# pir_sensor.net
KiCad netlist of a schematic drawn in Altium Designer
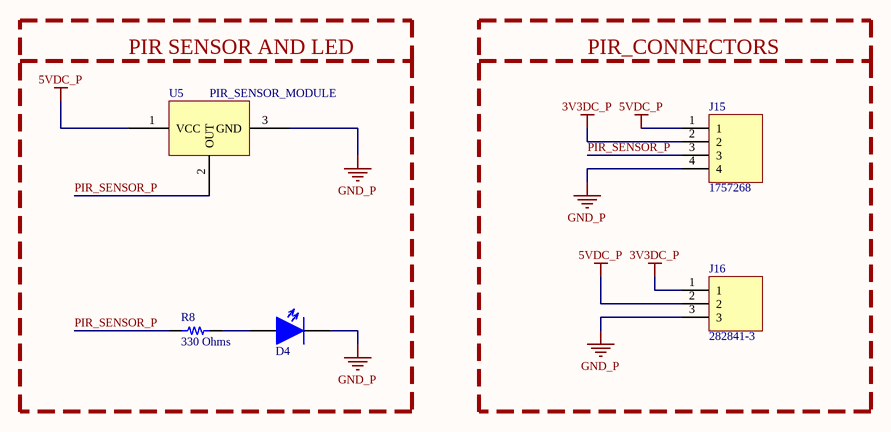
[diagram p0: pir_sensor.SchDoc]

(export (version "E")
  (design (tool "Eeschema 10.0.6"))
  (components
    (comp (ref "D4")
      (value "LTST-C171GKT")
      (footprint "LED_GREEN_0805")
      (description "Green 569nm LED Indication - Discrete 2.1V 0805 (2012 Metric)")
      (fields (field (name "MANUFACTURER") "Vishay Lite-On") (field (name "DESIGNED BY") "EMRE"))
      (libsource (lib "Udemy_library_Integrated_Library1") (part "LED GREEN 0805"))
    )
    (comp (ref "J15")
      (value "1757268")
      (footprint "CONNECTOR_4Pin")
      (description "Terminal Header; 12 A; 5.08 mm; 4; Solder Mount; 1.4 mm; 4 kV; 250 V; PBT")
      (fields (field (name "MANUFACTURER") "Phoenix Contact") (field (name "VOLTAGE") "300V"))
      (libsource (lib "Udemy_library_Integrated_Library1") (part "CONNECTOR_4Pin"))
    )
    (comp (ref "J16")
      (value "282841-3")
      (footprint "CONNECTOR_3Pin")
      (description "Conn Terminal Block 3 POS 5.08mm Solder ST Thru-Hole 17.5A/Contact")
      (fields (field (name "MANUFACTURER") "TE Connectivity") (field (name "VOLTAGE") "300V"))
      (libsource (lib "Udemy_library_Integrated_Library1") (part "CONNECTOR_3Pin"))
    )
    (comp (ref "R8")
      (value "330 Ohms")
      (footprint "RES 0805_2012")
      (description "RES SMD 330 OHM 5% 0.4W 0805")
      (fields (field (name "PART NUMBER") "ESR10EZPJ331") (field (name "MANUFACTURER") "Rohm Semiconductor"))
      (libsource (lib "Celestial Altium Library - altium_library") (part "Resistor"))
    )
    (comp (ref "U5")
      (value "PIR_SENSOR_MODULE")
      (footprint "PIR_SENSOR_MODULE")
      (libsource (lib "Udemy_library_Integrated_Library1") (part "PIR_SENSOR_MODULE"))
    )
  )
  (nets
    (net (code "1") (name "/PIR_SENSOR_P") (class "Default")
      (node (ref "J15") (pin "3") (pinfunction "3_3") (pintype "passive"))
      (node (ref "R8") (pin "1") (pinfunction "1_1") (pintype "passive"))
      (node (ref "U5") (pin "2") (pinfunction "OUT_2") (pintype "passive"))
    )
    (net (code "2") (name "3V3DC_P") (class "Default")
      (node (ref "J15") (pin "2") (pinfunction "2_2") (pintype "passive"))
      (node (ref "J16") (pin "1") (pinfunction "1_1") (pintype "passive"))
    )
    (net (code "3") (name "5VDC_P") (class "Default")
      (node (ref "J15") (pin "1") (pinfunction "1_1") (pintype "passive"))
      (node (ref "J16") (pin "2") (pinfunction "2_2") (pintype "passive"))
      (node (ref "U5") (pin "1") (pinfunction "VCC_1") (pintype "passive"))
    )
    (net (code "4") (name "GND_P") (class "Default")
      (node (ref "D4") (pin "1") (pinfunction "1_1") (pintype "passive"))
      (node (ref "J15") (pin "4") (pinfunction "4_4") (pintype "passive"))
      (node (ref "J16") (pin "3") (pinfunction "3_3") (pintype "passive"))
      (node (ref "U5") (pin "3") (pinfunction "GND_3") (pintype "passive"))
    )
    (net (code "5") (name "Net-(D4-Pad2)") (class "Default")
      (node (ref "D4") (pin "2") (pinfunction "2_2") (pintype "passive"))
      (node (ref "R8") (pin "2") (pinfunction "2_2") (pintype "passive"))
    )
  )
)
